# tetris_big_noregulator_PCBUSB.net
KiCad netlist of a schematic drawn in EAGLE
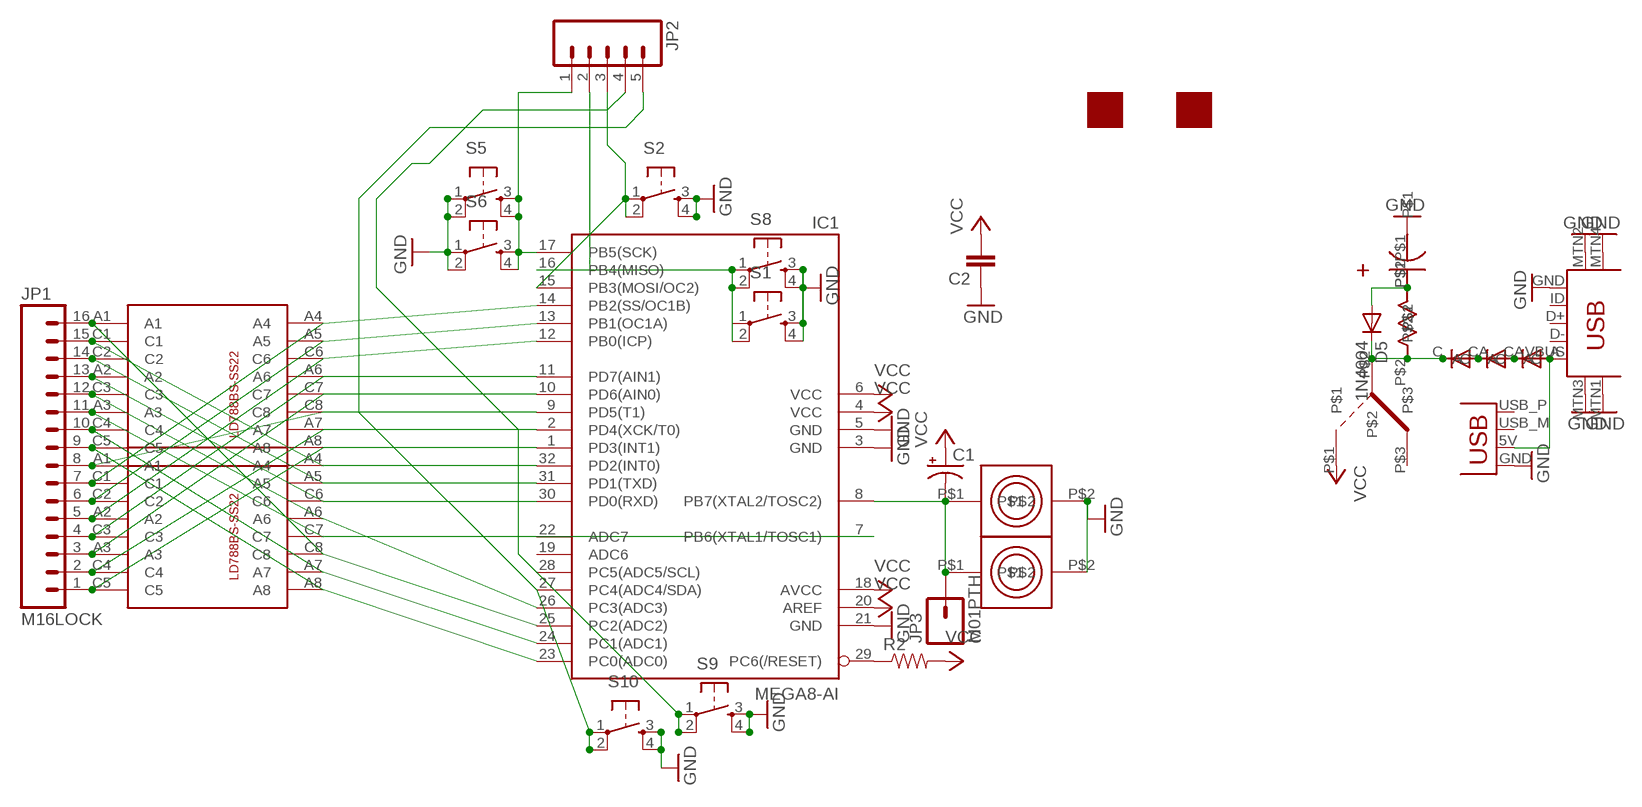
[diagram p0: schematic, sheet 1]

(export (version "E")
  (design (tool "Eeschema 10.0.6"))
  (components
    (comp (ref "C1")
      (value "CAP_POLPTH1")
      (footprint "eagle-import:CPOL-RADIAL-100UF-25V")
      (libsource (lib "eagle-import") (part "CAP_POLPTH1"))
    )
    (comp (ref "C2")
      (value "C-EU025-025X050")
      (footprint "eagle-import:C025-025X050")
      (libsource (lib "eagle-import") (part "C-EU025-025X050"))
    )
    (comp (ref "D5")
      (value "1N4004")
      (footprint "eagle-import:DO41-10")
      (libsource (lib "eagle-import") (part "1N4004"))
    )
    (comp (ref "IC1")
      (value "MEGA8-AI")
      (footprint "eagle-import:TQFP32-08")
      (fields
        (field (name "MPN") "ATMEGA8-16AU")
        (field (name "MPN_1") "ATMEGA8-16AU")
        (field (name "OC_FARNELL") "9171371")
        (field (name "OC_NEWARK") "73M8863")
      )
      (libsource (lib "eagle-import") (part "MEGA8-AI"))
    )
    (comp (ref "JP1")
      (value "M16LOCK")
      (footprint "eagle-import:1X16_LOCK")
      (libsource (lib "eagle-import") (part "M16LOCK"))
    )
    (comp (ref "JP2")
      (value "M05LOCK")
      (footprint "eagle-import:1X05_LOCK")
      (libsource (lib "eagle-import") (part "M05LOCK"))
    )
    (comp (ref "JP3")
      (value "M01PTH")
      (footprint "eagle-import:1X01")
      (libsource (lib "eagle-import") (part "M01PTH"))
    )
    (comp (ref "R2")
      (value "RESISTORPTH1")
      (footprint "eagle-import:AXIAL-0.3")
      (libsource (lib "eagle-import") (part "RESISTORPTH1"))
    )
    (comp (ref "S1")
      (value "TAC_SWITCHPTH")
      (footprint "eagle-import:TACTILE-PTH")
      (libsource (lib "eagle-import") (part "TAC_SWITCHPTH"))
    )
    (comp (ref "S2")
      (value "TAC_SWITCHPTH")
      (footprint "eagle-import:TACTILE-PTH")
      (libsource (lib "eagle-import") (part "TAC_SWITCHPTH"))
    )
    (comp (ref "S5")
      (value "TAC_SWITCHPTH")
      (footprint "eagle-import:TACTILE-PTH")
      (libsource (lib "eagle-import") (part "TAC_SWITCHPTH"))
    )
    (comp (ref "S6")
      (value "TAC_SWITCHPTH")
      (footprint "eagle-import:TACTILE-PTH")
      (libsource (lib "eagle-import") (part "TAC_SWITCHPTH"))
    )
    (comp (ref "S8")
      (value "TAC_SWITCHPTH")
      (footprint "eagle-import:TACTILE-PTH")
      (libsource (lib "eagle-import") (part "TAC_SWITCHPTH"))
    )
    (comp (ref "S9")
      (value "TAC_SWITCHPTH")
      (footprint "eagle-import:TACTILE-PTH")
      (libsource (lib "eagle-import") (part "TAC_SWITCHPTH"))
    )
    (comp (ref "S10")
      (value "TAC_SWITCHPTH")
      (footprint "eagle-import:TACTILE-PTH")
      (libsource (lib "eagle-import") (part "TAC_SWITCHPTH"))
    )
    (comp (ref "U$1")
      (value "LD-1088BS")
      (footprint "eagle-import:LD-1088BS")
      (libsource (lib "eagle-import") (part "LD-1088BS"))
    )
    (comp (ref "U$2")
      (value "LD-1088BS")
      (footprint "eagle-import:LD-1088BS")
      (libsource (lib "eagle-import") (part "LD-1088BS"))
    )
    (comp (ref "U$3")
      (value "LOGO")
      (footprint "eagle-import:LOGO")
      (libsource (lib "eagle-import") (part "LOGO"))
    )
    (comp (ref "U$4")
      (value "I-80450RF")
      (footprint "eagle-import:ISK4.1K_I-80450RF_I2G")
      (libsource (lib "eagle-import") (part "I-80450RF"))
    )
    (comp (ref "U$5")
      (value "NICHICON_12F")
      (footprint "eagle-import:NICHICON_10X30")
      (libsource (lib "eagle-import") (part "NICHICON_12F"))
    )
    (comp (ref "U$6")
      (value "LOGO")
      (footprint "eagle-import:LOGO")
      (libsource (lib "eagle-import") (part "LOGO"))
    )
    (comp (ref "U$7")
      (value "PIEZO_ROUND_PTH")
      (footprint "eagle-import:PIEZO_ROUND_ENCASED_PTH")
      (libsource (lib "eagle-import") (part "PIEZO_ROUND_PTH"))
    )
    (comp (ref "U$8")
      (value "R-7")
      (footprint "eagle-import:R-7")
      (libsource (lib "eagle-import") (part "R-7"))
    )
    (comp (ref "U$9")
      (value "SPST_BIG_PTH")
      (footprint "eagle-import:SWITCH_BIG")
      (libsource (lib "eagle-import") (part "SPST_BIG_PTH"))
    )
    (comp (ref "U$10")
      (value "D-6")
      (footprint "eagle-import:D-7.5")
      (libsource (lib "eagle-import") (part "D-6"))
    )
    (comp (ref "U$11")
      (value "D-6")
      (footprint "eagle-import:D-7.5")
      (libsource (lib "eagle-import") (part "D-6"))
    )
    (comp (ref "U$12")
      (value "D-6")
      (footprint "eagle-import:D-7.5")
      (libsource (lib "eagle-import") (part "D-6"))
    )
    (comp (ref "X1")
      (value "USB-MINIB-5PIN")
      (footprint "eagle-import:USB-MINIB")
      (libsource (lib "eagle-import") (part "USB-MINIB-5PIN"))
    )
    (comp (ref "X2")
      (value "USBPCB")
      (footprint "eagle-import:USB-A-PCB")
      (libsource (lib "eagle-import") (part "USBPCB"))
    )
  )
  (nets
    (net (code "1") (name "GND") (class "Default")
      (node (ref "C2") (pin "1") (pinfunction "1_1") (pintype "passive"))
      (node (ref "IC1") (pin "21") (pinfunction "GND_21") (pintype "power_in"))
      (node (ref "IC1") (pin "3") (pinfunction "GND_3") (pintype "power_in"))
      (node (ref "IC1") (pin "5") (pinfunction "GND_5") (pintype "power_in"))
      (node (ref "S1") (pin "3") (pinfunction "3_3") (pintype "passive"))
      (node (ref "S1") (pin "4") (pinfunction "4_4") (pintype "passive"))
      (node (ref "S10") (pin "3") (pinfunction "3_3") (pintype "passive"))
      (node (ref "S10") (pin "4") (pinfunction "4_4") (pintype "passive"))
      (node (ref "S2") (pin "3") (pinfunction "3_3") (pintype "passive"))
      (node (ref "S2") (pin "4") (pinfunction "4_4") (pintype "passive"))
      (node (ref "S5") (pin "1") (pinfunction "1_1") (pintype "passive"))
      (node (ref "S5") (pin "2") (pinfunction "2_2") (pintype "passive"))
      (node (ref "S6") (pin "1") (pinfunction "1_1") (pintype "passive"))
      (node (ref "S6") (pin "2") (pinfunction "2_2") (pintype "passive"))
      (node (ref "S8") (pin "3") (pinfunction "3_3") (pintype "passive"))
      (node (ref "S8") (pin "4") (pinfunction "4_4") (pintype "passive"))
      (node (ref "S9") (pin "3") (pinfunction "3_3") (pintype "passive"))
      (node (ref "S9") (pin "4") (pinfunction "4_4") (pintype "passive"))
      (node (ref "U$4") (pin "P$2") (pinfunction "P$2_P$2") (pintype "bidirectional"))
      (node (ref "U$5") (pin "P$1") (pinfunction "P$1_P$1") (pintype "bidirectional"))
      (node (ref "U$7") (pin "P$2") (pinfunction "P$2_P$2") (pintype "bidirectional"))
      (node (ref "X1") (pin "GND") (pinfunction "GND_GND") (pintype "bidirectional"))
      (node (ref "X1") (pin "MTN1") (pinfunction "MTN2_MTN1") (pintype "bidirectional"))
      (node (ref "X1") (pin "MTN2") (pinfunction "MTN3_MTN2") (pintype "bidirectional"))
      (node (ref "X1") (pin "MTN3") (pinfunction "MTN1_MTN3") (pintype "bidirectional"))
      (node (ref "X1") (pin "MTN4") (pinfunction "MTN4_MTN4") (pintype "bidirectional"))
      (node (ref "X2") (pin "GND") (pinfunction "GND_GND") (pintype "bidirectional"))
    )
    (net (code "2") (name "Net-(C1--)") (class "Default")
      (node (ref "C1") (pin "2") (pinfunction "-_2") (pintype "passive"))
      (node (ref "IC1") (pin "8") (pinfunction "PB7(XTAL2/TOSC2)_8") (pintype "bidirectional"))
      (node (ref "JP3") (pin "1") (pinfunction "1_1") (pintype "passive"))
      (node (ref "U$4") (pin "P$1") (pinfunction "P$1_P$1") (pintype "bidirectional"))
      (node (ref "U$7") (pin "P$1") (pinfunction "P$1_P$1") (pintype "bidirectional"))
    )
    (net (code "3") (name "Net-(D5-PadA)") (class "Default")
      (node (ref "D5") (pin "A") (pinfunction "A_A") (pintype "passive"))
      (node (ref "U$5") (pin "P$2") (pinfunction "P$2_P$2") (pintype "bidirectional"))
      (node (ref "U$8") (pin "P$1") (pinfunction "P$1_P$1") (pintype "bidirectional"))
    )
    (net (code "4") (name "Net-(D5-PadC)") (class "Default")
      (node (ref "D5") (pin "C") (pinfunction "C_C") (pintype "passive"))
      (node (ref "U$12") (pin "C") (pinfunction "C_C") (pintype "bidirectional"))
      (node (ref "U$8") (pin "P$2") (pinfunction "P$2_P$2") (pintype "bidirectional"))
      (node (ref "U$9") (pin "P$2") (pinfunction "P$2_P$2") (pintype "bidirectional"))
    )
    (net (code "5") (name "Net-(IC1-PB0(ICP))") (class "Default")
      (node (ref "IC1") (pin "12") (pinfunction "PB0(ICP)_12") (pintype "bidirectional"))
      (node (ref "JP1") (pin "5") (pinfunction "5_5") (pintype "passive"))
      (node (ref "U$1") (pin "A2") (pinfunction "A2_A2") (pintype "bidirectional"))
      (node (ref "U$2") (pin "C6") (pinfunction "C6_C6") (pintype "bidirectional"))
    )
    (net (code "6") (name "Net-(IC1-PB1(OC1A))") (class "Default")
      (node (ref "IC1") (pin "13") (pinfunction "PB1(OC1A)_13") (pintype "bidirectional"))
      (node (ref "JP1") (pin "6") (pinfunction "6_6") (pintype "passive"))
      (node (ref "U$1") (pin "C2") (pinfunction "C2_C2") (pintype "bidirectional"))
      (node (ref "U$2") (pin "A5") (pinfunction "A5_A5") (pintype "bidirectional"))
    )
    (net (code "7") (name "Net-(IC1-PB2(SS{slash}OC1B))") (class "Default")
      (node (ref "IC1") (pin "14") (pinfunction "PB2(SS/OC1B)_14") (pintype "bidirectional"))
      (node (ref "JP1") (pin "7") (pinfunction "7_7") (pintype "passive"))
      (node (ref "U$1") (pin "C1") (pinfunction "C1_C1") (pintype "bidirectional"))
      (node (ref "U$2") (pin "A4") (pinfunction "A4_A4") (pintype "bidirectional"))
    )
    (net (code "8") (name "Net-(IC1-PB3(MOSI{slash}OC2))") (class "Default")
      (node (ref "IC1") (pin "15") (pinfunction "PB3(MOSI/OC2)_15") (pintype "bidirectional"))
      (node (ref "JP2") (pin "3") (pinfunction "3_3") (pintype "passive"))
      (node (ref "S2") (pin "1") (pinfunction "1_1") (pintype "passive"))
      (node (ref "S2") (pin "2") (pinfunction "2_2") (pintype "passive"))
    )
    (net (code "9") (name "Net-(IC1-PB4(MISO))") (class "Default")
      (node (ref "IC1") (pin "16") (pinfunction "PB4(MISO)_16") (pintype "bidirectional"))
      (node (ref "JP2") (pin "2") (pinfunction "2_2") (pintype "passive"))
      (node (ref "S1") (pin "1") (pinfunction "1_1") (pintype "passive"))
      (node (ref "S1") (pin "2") (pinfunction "2_2") (pintype "passive"))
      (node (ref "S8") (pin "1") (pinfunction "1_1") (pintype "passive"))
      (node (ref "S8") (pin "2") (pinfunction "2_2") (pintype "passive"))
    )
    (net (code "10") (name "Net-(IC1-PB5(SCK))") (class "Default")
      (node (ref "IC1") (pin "17") (pinfunction "PB5(SCK)_17") (pintype "bidirectional"))
      (node (ref "JP2") (pin "1") (pinfunction "1_1") (pintype "passive"))
      (node (ref "S5") (pin "3") (pinfunction "3_3") (pintype "passive"))
      (node (ref "S5") (pin "4") (pinfunction "4_4") (pintype "passive"))
      (node (ref "S6") (pin "3") (pinfunction "3_3") (pintype "passive"))
      (node (ref "S6") (pin "4") (pinfunction "4_4") (pintype "passive"))
    )
    (net (code "11") (name "Net-(IC1-PB6(XTAL1{slash}TOSC1))") (class "Default")
      (node (ref "IC1") (pin "7") (pinfunction "PB6(XTAL1/TOSC1)_7") (pintype "bidirectional"))
      (node (ref "JP1") (pin "11") (pinfunction "11_11") (pintype "passive"))
      (node (ref "U$1") (pin "C7") (pinfunction "C7_C7") (pintype "bidirectional"))
      (node (ref "U$2") (pin "A3") (pinfunction "A3_A3") (pintype "bidirectional"))
    )
    (net (code "12") (name "Net-(IC1-PC0(ADC0))") (class "Default")
      (node (ref "IC1") (pin "23") (pinfunction "PC0(ADC0)_23") (pintype "bidirectional"))
      (node (ref "JP1") (pin "9") (pinfunction "9_9") (pintype "passive"))
      (node (ref "U$1") (pin "A8") (pinfunction "A8_A8") (pintype "bidirectional"))
      (node (ref "U$2") (pin "C5") (pinfunction "C5_C5") (pintype "bidirectional"))
    )
    (net (code "13") (name "Net-(IC1-PC1(ADC1))") (class "Default")
      (node (ref "IC1") (pin "24") (pinfunction "PC1(ADC1)_24") (pintype "bidirectional"))
      (node (ref "JP1") (pin "10") (pinfunction "10_10") (pintype "passive"))
      (node (ref "U$1") (pin "A7") (pinfunction "A7_A7") (pintype "bidirectional"))
      (node (ref "U$2") (pin "C4") (pinfunction "C4_C4") (pintype "bidirectional"))
    )
    (net (code "14") (name "Net-(IC1-PC2(ADC2))") (class "Default")
      (node (ref "IC1") (pin "25") (pinfunction "PC2(ADC2)_25") (pintype "bidirectional"))
      (node (ref "JP1") (pin "16") (pinfunction "16_16") (pintype "passive"))
      (node (ref "U$1") (pin "C8") (pinfunction "C8_C8") (pintype "bidirectional"))
      (node (ref "U$2") (pin "A1") (pinfunction "A1_A1") (pintype "bidirectional"))
    )
    (net (code "15") (name "Net-(IC1-PC3(ADC3))") (class "Default")
      (node (ref "IC1") (pin "26") (pinfunction "PC3(ADC3)_26") (pintype "bidirectional"))
      (node (ref "JP1") (pin "12") (pinfunction "12_12") (pintype "passive"))
      (node (ref "U$1") (pin "A6") (pinfunction "A6_A6") (pintype "bidirectional"))
      (node (ref "U$2") (pin "C3") (pinfunction "C3_C3") (pintype "bidirectional"))
    )
    (net (code "16") (name "Net-(IC1-PC4(ADC4{slash}SDA))") (class "Default")
      (node (ref "IC1") (pin "27") (pinfunction "PC4(ADC4/SDA)_27") (pintype "bidirectional"))
      (node (ref "JP2") (pin "5") (pinfunction "5_5") (pintype "passive"))
      (node (ref "S10") (pin "1") (pinfunction "1_1") (pintype "passive"))
      (node (ref "S10") (pin "2") (pinfunction "2_2") (pintype "passive"))
    )
    (net (code "17") (name "Net-(IC1-PC5(ADC5{slash}SCL))") (class "Default")
      (node (ref "IC1") (pin "28") (pinfunction "PC5(ADC5/SCL)_28") (pintype "bidirectional"))
      (node (ref "JP2") (pin "4") (pinfunction "4_4") (pintype "passive"))
      (node (ref "S9") (pin "1") (pinfunction "1_1") (pintype "passive"))
      (node (ref "S9") (pin "2") (pinfunction "2_2") (pintype "passive"))
    )
    (net (code "18") (name "Net-(IC1-PC6({slash}RESET))") (class "Default")
      (node (ref "IC1") (pin "29") (pinfunction "PC6(/RESET)_29") (pintype "bidirectional"))
      (node (ref "R2") (pin "P$1") (pinfunction "1_P$1") (pintype "passive"))
    )
    (net (code "19") (name "Net-(IC1-PD0(RXD))") (class "Default")
      (node (ref "IC1") (pin "30") (pinfunction "PD0(RXD)_30") (pintype "bidirectional"))
      (node (ref "JP1") (pin "13") (pinfunction "13_13") (pintype "passive"))
      (node (ref "U$1") (pin "C6") (pinfunction "C6_C6") (pintype "bidirectional"))
      (node (ref "U$2") (pin "A2") (pinfunction "A2_A2") (pintype "bidirectional"))
    )
    (net (code "20") (name "Net-(IC1-PD1(TXD))") (class "Default")
      (node (ref "IC1") (pin "31") (pinfunction "PD1(TXD)_31") (pintype "bidirectional"))
      (node (ref "JP1") (pin "14") (pinfunction "14_14") (pintype "passive"))
      (node (ref "U$1") (pin "A5") (pinfunction "A5_A5") (pintype "bidirectional"))
      (node (ref "U$2") (pin "C2") (pinfunction "C2_C2") (pintype "bidirectional"))
    )
    (net (code "21") (name "Net-(IC1-PD2(INT0))") (class "Default")
      (node (ref "IC1") (pin "32") (pinfunction "PD2(INT0)_32") (pintype "bidirectional"))
      (node (ref "JP1") (pin "15") (pinfunction "15_15") (pintype "passive"))
      (node (ref "U$1") (pin "A4") (pinfunction "A4_A4") (pintype "bidirectional"))
      (node (ref "U$2") (pin "C1") (pinfunction "C1_C1") (pintype "bidirectional"))
    )
    (net (code "22") (name "Net-(IC1-PD3(INT1))") (class "Default")
      (node (ref "IC1") (pin "1") (pinfunction "PD3(INT1)_1") (pintype "bidirectional"))
      (node (ref "JP1") (pin "1") (pinfunction "1_1") (pintype "passive"))
      (node (ref "U$1") (pin "C5") (pinfunction "C5_C5") (pintype "bidirectional"))
      (node (ref "U$2") (pin "A8") (pinfunction "A8_A8") (pintype "bidirectional"))
    )
    (net (code "23") (name "Net-(IC1-PD4(XCK{slash}T0))") (class "Default")
      (node (ref "IC1") (pin "2") (pinfunction "PD4(XCK/T0)_2") (pintype "bidirectional"))
      (node (ref "JP1") (pin "2") (pinfunction "2_2") (pintype "passive"))
      (node (ref "U$1") (pin "C4") (pinfunction "C4_C4") (pintype "bidirectional"))
      (node (ref "U$2") (pin "A7") (pinfunction "A7_A7") (pintype "bidirectional"))
    )
    (net (code "24") (name "Net-(IC1-PD5(T1))") (class "Default")
      (node (ref "IC1") (pin "9") (pinfunction "PD5(T1)_9") (pintype "bidirectional"))
      (node (ref "JP1") (pin "8") (pinfunction "8_8") (pintype "passive"))
      (node (ref "U$1") (pin "A1") (pinfunction "A1_A1") (pintype "bidirectional"))
      (node (ref "U$2") (pin "C8") (pinfunction "C8_C8") (pintype "bidirectional"))
    )
    (net (code "25") (name "Net-(IC1-PD6(AIN0))") (class "Default")
      (node (ref "IC1") (pin "10") (pinfunction "PD6(AIN0)_10") (pintype "bidirectional"))
      (node (ref "JP1") (pin "3") (pinfunction "3_3") (pintype "passive"))
      (node (ref "U$1") (pin "A3") (pinfunction "A3_A3") (pintype "bidirectional"))
      (node (ref "U$2") (pin "C7") (pinfunction "C7_C7") (pintype "bidirectional"))
    )
    (net (code "26") (name "Net-(IC1-PD7(AIN1))") (class "Default")
      (node (ref "IC1") (pin "11") (pinfunction "PD7(AIN1)_11") (pintype "bidirectional"))
      (node (ref "JP1") (pin "4") (pinfunction "4_4") (pintype "passive"))
      (node (ref "U$1") (pin "C3") (pinfunction "C3_C3") (pintype "bidirectional"))
      (node (ref "U$2") (pin "A6") (pinfunction "A6_A6") (pintype "bidirectional"))
    )
    (net (code "27") (name "Net-(U$10-PadC)") (class "Default")
      (node (ref "U$10") (pin "C") (pinfunction "C_C") (pintype "bidirectional"))
      (node (ref "U$11") (pin "A") (pinfunction "A_A") (pintype "bidirectional"))
    )
    (net (code "28") (name "Net-(U$11-PadC)") (class "Default")
      (node (ref "U$11") (pin "C") (pinfunction "C_C") (pintype "bidirectional"))
      (node (ref "U$12") (pin "A") (pinfunction "A_A") (pintype "bidirectional"))
    )
    (net (code "29") (name "Net-(X2-VBUS)") (class "Default")
      (node (ref "U$10") (pin "A") (pinfunction "A_A") (pintype "bidirectional"))
      (node (ref "X1") (pin "VBUS") (pinfunction "VBUS_VBUS") (pintype "bidirectional"))
      (node (ref "X2") (pin "5V") (pinfunction "VBUS_5V") (pintype "bidirectional"))
    )
    (net (code "30") (name "VCC") (class "Default")
      (node (ref "C1") (pin "1") (pinfunction "+_1") (pintype "passive"))
      (node (ref "C2") (pin "2") (pinfunction "2_2") (pintype "passive"))
      (node (ref "IC1") (pin "18") (pinfunction "AVCC_18") (pintype "power_in"))
      (node (ref "IC1") (pin "20") (pinfunction "AREF_20") (pintype "passive"))
      (node (ref "IC1") (pin "4") (pinfunction "VCC_4") (pintype "power_in"))
      (node (ref "IC1") (pin "6") (pinfunction "VCC_6") (pintype "power_in"))
      (node (ref "R2") (pin "P$2") (pinfunction "2_P$2") (pintype "passive"))
      (node (ref "U$9") (pin "P$1") (pinfunction "P$1_P$1") (pintype "bidirectional"))
    )
    (net (code "31") (name "unconnected-(IC1-ADC6-Pad19)") (class "Default")
      (node (ref "IC1") (pin "19") (pinfunction "ADC6_19") (pintype "bidirectional"))
    )
    (net (code "32") (name "unconnected-(IC1-ADC7-Pad22)") (class "Default")
      (node (ref "IC1") (pin "22") (pinfunction "ADC7_22") (pintype "bidirectional"))
    )
    (net (code "33") (name "unconnected-(U$9-PadP$3)") (class "Default")
      (node (ref "U$9") (pin "P$3") (pinfunction "P$3_P$3") (pintype "bidirectional"))
    )
    (net (code "34") (name "unconnected-(X1-PadD+)") (class "Default")
      (node (ref "X1") (pin "D+") (pinfunction "D+_D+") (pintype "bidirectional"))
    )
    (net (code "35") (name "unconnected-(X1-PadD-)") (class "Default")
      (node (ref "X1") (pin "D-") (pinfunction "D-_D-") (pintype "bidirectional"))
    )
    (net (code "36") (name "unconnected-(X1-PadID)") (class "Default")
      (node (ref "X1") (pin "ID") (pinfunction "ID_ID") (pintype "bidirectional"))
    )
    (net (code "37") (name "unconnected-(X2-D+-PadUSB_P)") (class "Default")
      (node (ref "X2") (pin "USB_P") (pinfunction "D+_USB_P") (pintype "bidirectional"))
    )
    (net (code "38") (name "unconnected-(X2-D--PadUSB_M)") (class "Default")
      (node (ref "X2") (pin "USB_M") (pinfunction "D-_USB_M") (pintype "bidirectional"))
    )
  )
)
